# singlecoil.net
KiCad netlist of a schematic drawn in EAGLE
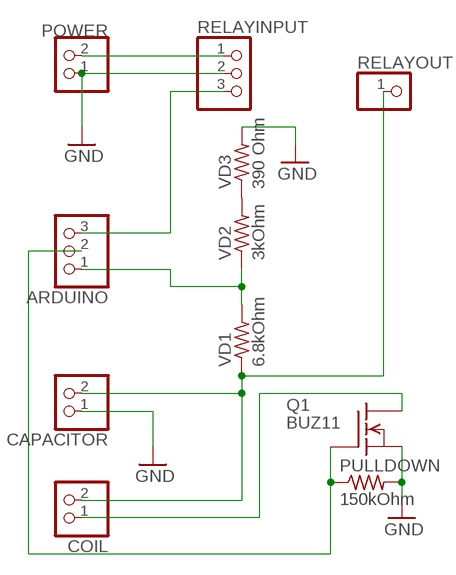
[diagram p0: schematic, sheet 1]

(export (version "E")
  (design (tool "Eeschema 10.0.6"))
  (components
    (comp (ref "ARDUINO")
      (value "PINHD-1X3")
      (footprint "eagle-import:1X03")
      (libsource (lib "eagle-import") (part "PINHD-1X3"))
    )
    (comp (ref "CAPACITOR")
      (value "PINHD-1X2")
      (footprint "eagle-import:1X02")
      (libsource (lib "eagle-import") (part "PINHD-1X2"))
    )
    (comp (ref "COIL")
      (value "PINHD-1X2")
      (footprint "eagle-import:1X02")
      (libsource (lib "eagle-import") (part "PINHD-1X2"))
    )
    (comp (ref "POWER")
      (value "PINHD-1X2")
      (footprint "eagle-import:1X02")
      (libsource (lib "eagle-import") (part "PINHD-1X2"))
    )
    (comp (ref "PULLDOWN")
      (value "150kOhm")
      (footprint "eagle-import:0204V")
      (libsource (lib "eagle-import") (part "R-US_0204/2V"))
    )
    (comp (ref "Q1")
      (value "BUZ11")
      (footprint "eagle-import:TO220")
      (libsource (lib "eagle-import") (part "BUZ11"))
    )
    (comp (ref "RELAYINPUT")
      (value "PINHD-1X3")
      (footprint "eagle-import:1X03")
      (libsource (lib "eagle-import") (part "PINHD-1X3"))
    )
    (comp (ref "RELAYOUT")
      (value "PINHD-1X1")
      (footprint "eagle-import:1X01")
      (libsource (lib "eagle-import") (part "PINHD-1X1"))
    )
    (comp (ref "VD1")
      (value "6.8kOhm")
      (footprint "eagle-import:0204V")
      (libsource (lib "eagle-import") (part "R-US_0204/2V"))
    )
    (comp (ref "VD2")
      (value "3kOhm")
      (footprint "eagle-import:0204V")
      (libsource (lib "eagle-import") (part "R-US_0204/2V"))
    )
    (comp (ref "VD3")
      (value "390 Ohm")
      (footprint "eagle-import:0204V")
      (libsource (lib "eagle-import") (part "R-US_0204/2V"))
    )
  )
  (nets
    (net (code "1") (name "GND") (class "Default")
      (node (ref "CAPACITOR") (pin "1") (pinfunction "1_1") (pintype "passive"))
      (node (ref "POWER") (pin "1") (pinfunction "1_1") (pintype "passive"))
      (node (ref "PULLDOWN") (pin "2") (pinfunction "2_2") (pintype "passive"))
      (node (ref "Q1") (pin "3") (pinfunction "S_3") (pintype "passive"))
      (node (ref "RELAYINPUT") (pin "2") (pinfunction "2_2") (pintype "passive"))
      (node (ref "VD3") (pin "2") (pinfunction "2_2") (pintype "passive"))
    )
    (net (code "2") (name "Net-(ARDUINO-Pad1)") (class "Default")
      (node (ref "ARDUINO") (pin "1") (pinfunction "1_1") (pintype "passive"))
      (node (ref "VD1") (pin "2") (pinfunction "2_2") (pintype "passive"))
      (node (ref "VD2") (pin "1") (pinfunction "1_1") (pintype "passive"))
    )
    (net (code "3") (name "Net-(ARDUINO-Pad3)") (class "Default")
      (node (ref "ARDUINO") (pin "3") (pinfunction "3_3") (pintype "passive"))
      (node (ref "RELAYINPUT") (pin "3") (pinfunction "3_3") (pintype "passive"))
    )
    (net (code "4") (name "Net-(CAPACITOR-Pad2)") (class "Default")
      (node (ref "CAPACITOR") (pin "2") (pinfunction "2_2") (pintype "passive"))
      (node (ref "COIL") (pin "2") (pinfunction "2_2") (pintype "passive"))
      (node (ref "RELAYOUT") (pin "1") (pinfunction "1_1") (pintype "passive"))
      (node (ref "VD1") (pin "1") (pinfunction "1_1") (pintype "passive"))
    )
    (net (code "5") (name "Net-(POWER-Pad2)") (class "Default")
      (node (ref "POWER") (pin "2") (pinfunction "2_2") (pintype "passive"))
      (node (ref "RELAYINPUT") (pin "1") (pinfunction "1_1") (pintype "passive"))
    )
    (net (code "6") (name "Net-(Q1-D)") (class "Default")
      (node (ref "COIL") (pin "1") (pinfunction "1_1") (pintype "passive"))
      (node (ref "Q1") (pin "2") (pinfunction "D_2") (pintype "passive"))
    )
    (net (code "7") (name "Net-(Q1-G)") (class "Default")
      (node (ref "ARDUINO") (pin "2") (pinfunction "2_2") (pintype "passive"))
      (node (ref "PULLDOWN") (pin "1") (pinfunction "1_1") (pintype "passive"))
      (node (ref "Q1") (pin "1") (pinfunction "G_1") (pintype "passive"))
    )
    (net (code "8") (name "Net-(VD2-Pad2)") (class "Default")
      (node (ref "VD2") (pin "2") (pinfunction "2_2") (pintype "passive"))
      (node (ref "VD3") (pin "1") (pinfunction "1_1") (pintype "passive"))
    )
  )
)
